# 10_ARDUINO.net
KiCad netlist of a schematic drawn in EAGLE
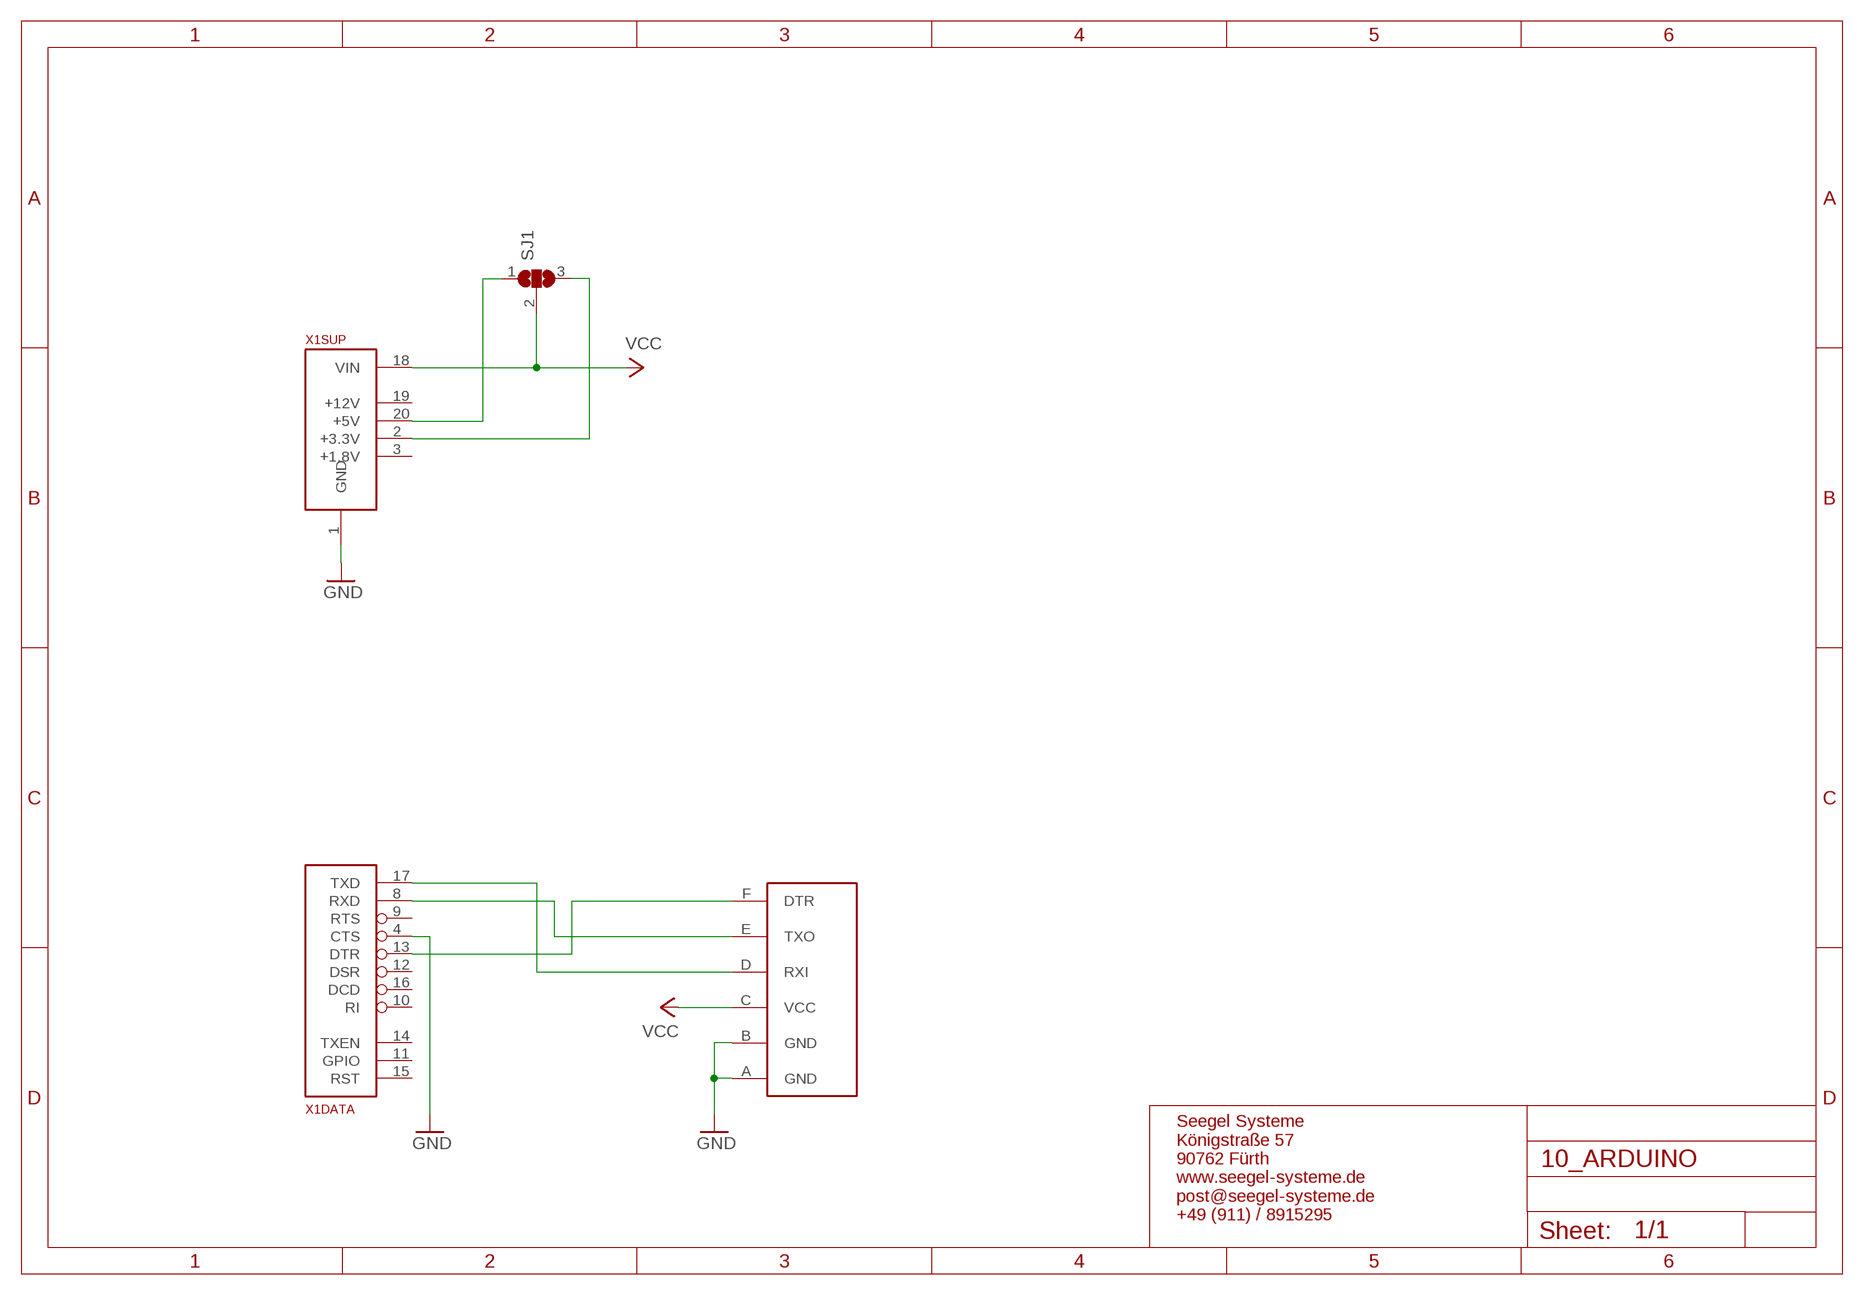
[diagram p0: schematic, sheet 1]

(export (version "E")
  (design (tool "Eeschema 10.0.6"))
  (components
    (comp (ref "M1")
      (value "ARDUINO_PROMINI")
      (footprint "eagle-import:ARDUINO_PROMINI")
      (libsource (lib "eagle-import") (part "ARDUINO_PROMINI"))
    )
    (comp (ref "SJ1")
      (value "SJ2W")
      (footprint "eagle-import:SJ_2")
      (libsource (lib "eagle-import") (part "SJ2W"))
    )
    (comp (ref "X1")
      (value "ALLSERIALSLAVE")
      (footprint "eagle-import:DAUGHTER-THT")
      (libsource (lib "eagle-import") (part "ALLSERIALSLAVE"))
    )
  )
  (nets
    (net (code "1") (name "GND") (class "Default")
      (node (ref "M1") (pin "A") (pinfunction "GND_A") (pintype "bidirectional"))
      (node (ref "M1") (pin "B") (pinfunction "GND_B") (pintype "bidirectional"))
      (node (ref "X1") (pin "1") (pinfunction "GND_1") (pintype "bidirectional"))
      (node (ref "X1") (pin "4") (pinfunction "CTS_4") (pintype "input"))
    )
    (net (code "2") (name "Net-(M1-DTR)") (class "Default")
      (node (ref "M1") (pin "F") (pinfunction "DTR_F") (pintype "bidirectional"))
      (node (ref "X1") (pin "13") (pinfunction "DTR_13") (pintype "output"))
    )
    (net (code "3") (name "Net-(M1-RXI)") (class "Default")
      (node (ref "M1") (pin "D") (pinfunction "RXI_D") (pintype "bidirectional"))
      (node (ref "X1") (pin "17") (pinfunction "TXD_17") (pintype "output"))
    )
    (net (code "4") (name "Net-(M1-TXO)") (class "Default")
      (node (ref "M1") (pin "E") (pinfunction "TXO_E") (pintype "bidirectional"))
      (node (ref "X1") (pin "8") (pinfunction "RXD_8") (pintype "input"))
    )
    (net (code "5") (name "Net-(X1B-+3.3V)") (class "Default")
      (node (ref "SJ1") (pin "3") (pinfunction "3_3") (pintype "passive"))
      (node (ref "X1") (pin "2") (pinfunction "+3.3V_2") (pintype "bidirectional"))
    )
    (net (code "6") (name "Net-(X1B-+5V)") (class "Default")
      (node (ref "SJ1") (pin "1") (pinfunction "1_1") (pintype "passive"))
      (node (ref "X1") (pin "20") (pinfunction "+5V_20") (pintype "bidirectional"))
    )
    (net (code "7") (name "VCC") (class "Default")
      (node (ref "M1") (pin "C") (pinfunction "VCC_C") (pintype "bidirectional"))
      (node (ref "SJ1") (pin "2") (pinfunction "2_2") (pintype "passive"))
      (node (ref "X1") (pin "18") (pinfunction "VIN_18") (pintype "bidirectional"))
    )
    (net (code "8") (name "unconnected-(X1A-DCD-Pad16)") (class "Default")
      (node (ref "X1") (pin "16") (pinfunction "DCD_16") (pintype "input"))
    )
    (net (code "9") (name "unconnected-(X1A-DSR-Pad12)") (class "Default")
      (node (ref "X1") (pin "12") (pinfunction "DSR_12") (pintype "input"))
    )
    (net (code "10") (name "unconnected-(X1A-GPIO-Pad11)") (class "Default")
      (node (ref "X1") (pin "11") (pinfunction "GPIO_11") (pintype "bidirectional"))
    )
    (net (code "11") (name "unconnected-(X1A-RI-Pad10)") (class "Default")
      (node (ref "X1") (pin "10") (pinfunction "RI_10") (pintype "input"))
    )
    (net (code "12") (name "unconnected-(X1A-RST-Pad15)") (class "Default")
      (node (ref "X1") (pin "15") (pinfunction "RST_15") (pintype "bidirectional"))
    )
    (net (code "13") (name "unconnected-(X1A-RTS-Pad9)") (class "Default")
      (node (ref "X1") (pin "9") (pinfunction "RTS_9") (pintype "output"))
    )
    (net (code "14") (name "unconnected-(X1A-TXEN-Pad14)") (class "Default")
      (node (ref "X1") (pin "14") (pinfunction "TXEN_14") (pintype "output"))
    )
    (net (code "15") (name "unconnected-(X1B-+1.8V-Pad3)") (class "Default")
      (node (ref "X1") (pin "3") (pinfunction "+1.8V_3") (pintype "bidirectional"))
    )
    (net (code "16") (name "unconnected-(X1B-+12V-Pad19)") (class "Default")
      (node (ref "X1") (pin "19") (pinfunction "+12V_19") (pintype "bidirectional"))
    )
  )
)
